# 01rng.net
KiCad netlist of a schematic drawn in Altium Designer
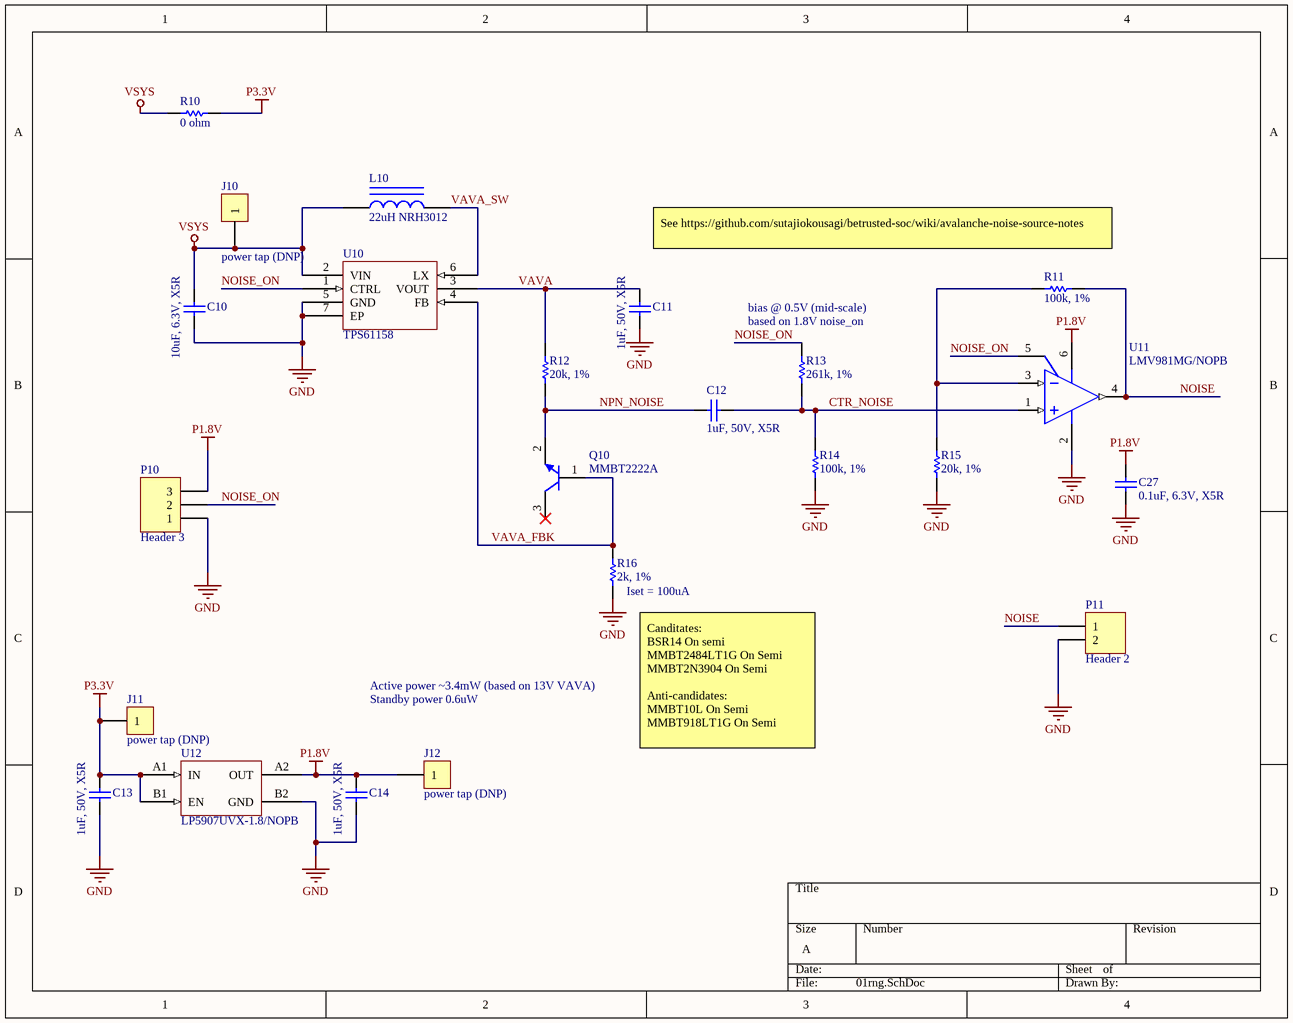
[diagram p0: 01rng.SchDoc]

(export (version "E")
  (design (tool "Eeschema 10.0.6"))
  (components
    (comp (ref "C10")
      (value "10uF, 6.3V, X5R")
      (footprint "B_CAP0603")
      (description "Capacitor (Semiconductor SIM Model)")
      (fields (field (name "MPN") "CL10A106MQ8NNNC"))
      (libsource (lib "Miscellaneous Devices") (part "Cap Semi"))
    )
    (comp (ref "C11")
      (value "1uF, 50V, X5R")
      (footprint "B_CAP0603")
      (description "Capacitor (Semiconductor SIM Model)")
      (fields (field (name "MPN") "CL10A105KB8NNNC"))
      (libsource (lib "Miscellaneous Devices") (part "Cap Semi"))
    )
    (comp (ref "C12")
      (value "1uF, 50V, X5R")
      (footprint "B_CAP0603")
      (description "Capacitor (Semiconductor SIM Model)")
      (fields (field (name "MPN") "CL10A105KB8NNNC"))
      (libsource (lib "Miscellaneous Devices") (part "Cap Semi"))
    )
    (comp (ref "C13")
      (value "1uF, 50V, X5R")
      (footprint "B_CAP0603")
      (description "Capacitor (Semiconductor SIM Model)")
      (fields (field (name "MPN") "CL10A105KB8NNNC"))
      (libsource (lib "Miscellaneous Devices") (part "Cap Semi"))
    )
    (comp (ref "C14")
      (value "1uF, 50V, X5R")
      (footprint "B_CAP0603")
      (description "Capacitor (Semiconductor SIM Model)")
      (fields (field (name "MPN") "CL10A105KB8NNNC"))
      (libsource (lib "Miscellaneous Devices") (part "Cap Semi"))
    )
    (comp (ref "C27")
      (value "0.1uF, 6.3V, X5R")
      (footprint "B_CAP0603")
      (description "Capacitor (Semiconductor SIM Model)")
      (fields (field (name "MPN") "ANY"))
      (libsource (lib "Miscellaneous Devices") (part "Cap Semi"))
    )
    (comp (ref "J10")
      (value "power tap (DNP)")
      (footprint "RESTAP-0603")
      (description "Connector")
      (fields (field (name "MPN") "DNP"))
      (libsource (lib "") (part "CON1_1"))
    )
    (comp (ref "J11")
      (value "power tap (DNP)")
      (footprint "RESTAP-0603")
      (description "Connector")
      (fields (field (name "MPN") "DNP"))
      (libsource (lib "*") (part "CON1"))
    )
    (comp (ref "J12")
      (value "power tap (DNP)")
      (footprint "RESTAP-0603")
      (description "Connector")
      (fields (field (name "MPN") "DNP"))
      (libsource (lib "*") (part "CON1"))
    )
    (comp (ref "L10")
      (value "22uH NRH3012")
      (footprint "TAIYO_NRH3012")
      (description "Magnetic-Core Inductor")
      (fields (field (name "MPN") "NRH3012T220MN"))
      (libsource (lib "Miscellaneous Devices") (part "Inductor Iron"))
    )
    (comp (ref "P10")
      (value "Header 3")
      (footprint "HDR1X3")
      (description "Header, 3-Pin")
      (fields (field (name "PUBLISHER") "Altium Limited"))
      (libsource (lib "Miscellaneous Connectors") (part "Header 3"))
    )
    (comp (ref "P11")
      (value "Header 2")
      (footprint "HDR1X2")
      (description "Header, 2-Pin")
      (fields (field (name "PUBLISHER") "Altium Limited"))
      (libsource (lib "Miscellaneous Connectors") (part "Header 2"))
    )
    (comp (ref "Q10")
      (value "MMBT2222A")
      (footprint "ONSC-SOT-23-3-318-08_V")
      (libsource (lib "ONSC-NPN-B1E2C3-3") (part "ONSC-NPN-B1E2C3-3"))
    )
    (comp (ref "R10")
      (value "0 ohm")
      (footprint "B_RES0603")
      (description "Resistor")
      (fields (field (name "MPN") "ANY"))
      (libsource (lib "Miscellaneous Devices") (part "Res1"))
    )
    (comp (ref "R11")
      (value "100k, 1%")
      (footprint "B_RES0402")
      (description "Resistor")
      (fields (field (name "MPN") "ANY"))
      (libsource (lib "Miscellaneous Devices") (part "Res1"))
    )
    (comp (ref "R12")
      (value "20k, 1%")
      (footprint "B_RES0402")
      (description "Resistor")
      (fields (field (name "MPN") "ANY"))
      (libsource (lib "Miscellaneous Devices") (part "Res1"))
    )
    (comp (ref "R13")
      (value "261k, 1%")
      (footprint "B_RES0402")
      (description "Resistor")
      (fields (field (name "MPN") "ANY"))
      (libsource (lib "Miscellaneous Devices") (part "Res1"))
    )
    (comp (ref "R14")
      (value "100k, 1%")
      (footprint "B_RES0402")
      (description "Resistor")
      (fields (field (name "MPN") "ANY"))
      (libsource (lib "Miscellaneous Devices") (part "Res1"))
    )
    (comp (ref "R15")
      (value "20k, 1%")
      (footprint "B_RES0402")
      (description "Resistor")
      (fields (field (name "MPN") "ANY"))
      (libsource (lib "Miscellaneous Devices") (part "Res1"))
    )
    (comp (ref "R16")
      (value "2k, 1%")
      (footprint "B_RES0402")
      (description "Resistor")
      (fields (field (name "MPN") "ANY"))
      (libsource (lib "Miscellaneous Devices") (part "Res1"))
    )
    (comp (ref "U10")
      (value "TPS61158")
      (footprint "SON65P200X80_HS-7N")
      (description "30V WLED driver with integrated power diode")
      (fields (field (name "MPN") "TPS61158DRVR"))
      (libsource (lib "commonsch-new") (part "TPS61158"))
    )
    (comp (ref "U11")
      (value "LMV981MG/NOPB")
      (footprint "DCK0006A_N")
      (description "Single 1.8V, RRIO Operational Amplifiers with Shutdown, 6-pin SC-70, Pb-Free")
      (libsource (lib "Altium Content Vault") (part "AMP-OPA-LMV981-6"))
    )
    (comp (ref "U12")
      (value "LP5907UVX-1.8/NOPB")
      (footprint "TI_YKE004")
      (description "Ultra low-noise 250mA LDO for RF and analog in DSBGA")
      (libsource (lib "commonsch-new") (part "LP5907UVX"))
    )
  )
  (nets
    (net (code "1") (name "/CTR_NOISE") (class "Default")
      (node (ref "C12") (pin "2") (pinfunction "2_2") (pintype "passive"))
      (node (ref "R13") (pin "1") (pinfunction "1_1") (pintype "passive"))
      (node (ref "R14") (pin "2") (pinfunction "2_2") (pintype "passive"))
      (node (ref "U11") (pin "1") (pinfunction "IN+_1") (pintype "input"))
    )
    (net (code "2") (name "/NOISE") (class "Default")
      (node (ref "P11") (pin "1") (pinfunction "1_1") (pintype "passive"))
      (node (ref "R11") (pin "1") (pinfunction "1_1") (pintype "passive"))
      (node (ref "U11") (pin "4") (pinfunction "OUT_4") (pintype "output"))
    )
    (net (code "3") (name "/NOISE_ON") (class "Default")
      (node (ref "P10") (pin "2") (pinfunction "2_2") (pintype "passive"))
      (node (ref "R13") (pin "2") (pinfunction "2_2") (pintype "passive"))
      (node (ref "U10") (pin "1") (pinfunction "CTRL_1") (pintype "input"))
      (node (ref "U11") (pin "5") (pinfunction "~{SHDN}_5") (pintype "passive"))
    )
    (net (code "4") (name "/NPN_NOISE") (class "Default")
      (node (ref "C12") (pin "1") (pinfunction "1_1") (pintype "passive"))
      (node (ref "Q10") (pin "2") (pinfunction "E_2") (pintype "passive"))
      (node (ref "R12") (pin "1") (pinfunction "1_1") (pintype "passive"))
    )
    (net (code "5") (name "/VAVA") (class "Default")
      (node (ref "C11") (pin "1") (pinfunction "1_1") (pintype "passive"))
      (node (ref "R12") (pin "2") (pinfunction "2_2") (pintype "passive"))
      (node (ref "U10") (pin "3") (pinfunction "VOUT_3") (pintype "power_in"))
    )
    (net (code "6") (name "/VAVA_FBK") (class "Default")
      (node (ref "Q10") (pin "1") (pinfunction "B_1") (pintype "passive"))
      (node (ref "R16") (pin "2") (pinfunction "2_2") (pintype "passive"))
      (node (ref "U10") (pin "4") (pinfunction "FB_4") (pintype "input"))
    )
    (net (code "7") (name "/VAVA_SW") (class "Default")
      (node (ref "L10") (pin "2") (pinfunction "2_2") (pintype "passive"))
      (node (ref "U10") (pin "6") (pinfunction "LX_6") (pintype "input"))
    )
    (net (code "8") (name "GND") (class "Default")
      (node (ref "C10") (pin "2") (pinfunction "2_2") (pintype "passive"))
      (node (ref "C11") (pin "2") (pinfunction "2_2") (pintype "passive"))
      (node (ref "C13") (pin "2") (pinfunction "2_2") (pintype "passive"))
      (node (ref "C14") (pin "2") (pinfunction "2_2") (pintype "passive"))
      (node (ref "C27") (pin "1") (pinfunction "1_1") (pintype "passive"))
      (node (ref "P10") (pin "1") (pinfunction "1_1") (pintype "passive"))
      (node (ref "P11") (pin "2") (pinfunction "2_2") (pintype "passive"))
      (node (ref "R14") (pin "1") (pinfunction "1_1") (pintype "passive"))
      (node (ref "R15") (pin "1") (pinfunction "1_1") (pintype "passive"))
      (node (ref "R16") (pin "1") (pinfunction "1_1") (pintype "passive"))
      (node (ref "U10") (pin "5") (pinfunction "GND_5") (pintype "power_in"))
      (node (ref "U10") (pin "7") (pinfunction "EP_7") (pintype "power_in"))
      (node (ref "U11") (pin "2") (pinfunction "GND_2") (pintype "power_in"))
      (node (ref "U12") (pin "B2") (pinfunction "GND_B2") (pintype "power_in"))
    )
    (net (code "9") (name "Net-(U11-IN-)") (class "Default")
      (node (ref "R11") (pin "2") (pinfunction "2_2") (pintype "passive"))
      (node (ref "R15") (pin "2") (pinfunction "2_2") (pintype "passive"))
      (node (ref "U11") (pin "3") (pinfunction "IN-_3") (pintype "input"))
    )
    (net (code "10") (name "P1.8V") (class "Default")
      (node (ref "C14") (pin "1") (pinfunction "1_1") (pintype "passive"))
      (node (ref "C27") (pin "2") (pinfunction "2_2") (pintype "passive"))
      (node (ref "J12") (pin "1") (pinfunction "1_1") (pintype "passive"))
      (node (ref "P10") (pin "3") (pinfunction "3_3") (pintype "passive"))
      (node (ref "U11") (pin "6") (pinfunction "VDD_6") (pintype "power_in"))
      (node (ref "U12") (pin "A2") (pinfunction "OUT_A2") (pintype "power_in"))
    )
    (net (code "11") (name "P3.3V") (class "Default")
      (node (ref "C13") (pin "1") (pinfunction "1_1") (pintype "passive"))
      (node (ref "J11") (pin "1") (pinfunction "1_1") (pintype "passive"))
      (node (ref "R10") (pin "2") (pinfunction "2_2") (pintype "passive"))
      (node (ref "U12") (pin "A1") (pinfunction "IN_A1") (pintype "input"))
      (node (ref "U12") (pin "B1") (pinfunction "EN_B1") (pintype "input"))
    )
    (net (code "12") (name "VSYS") (class "Default")
      (node (ref "C10") (pin "1") (pinfunction "1_1") (pintype "passive"))
      (node (ref "J10") (pin "1") (pinfunction "1_1") (pintype "passive"))
      (node (ref "L10") (pin "1") (pinfunction "1_1") (pintype "passive"))
      (node (ref "R10") (pin "1") (pinfunction "1_1") (pintype "passive"))
      (node (ref "U10") (pin "2") (pinfunction "VIN_2") (pintype "power_in"))
    )
    (net (code "13") (name "unconnected-(Q10-C-Pad3)") (class "Default")
      (node (ref "Q10") (pin "3") (pinfunction "C_3") (pintype "passive+no_connect"))
    )
  )
)
